# Test_Board.net
KiCad netlist of a schematic drawn in Altium Designer
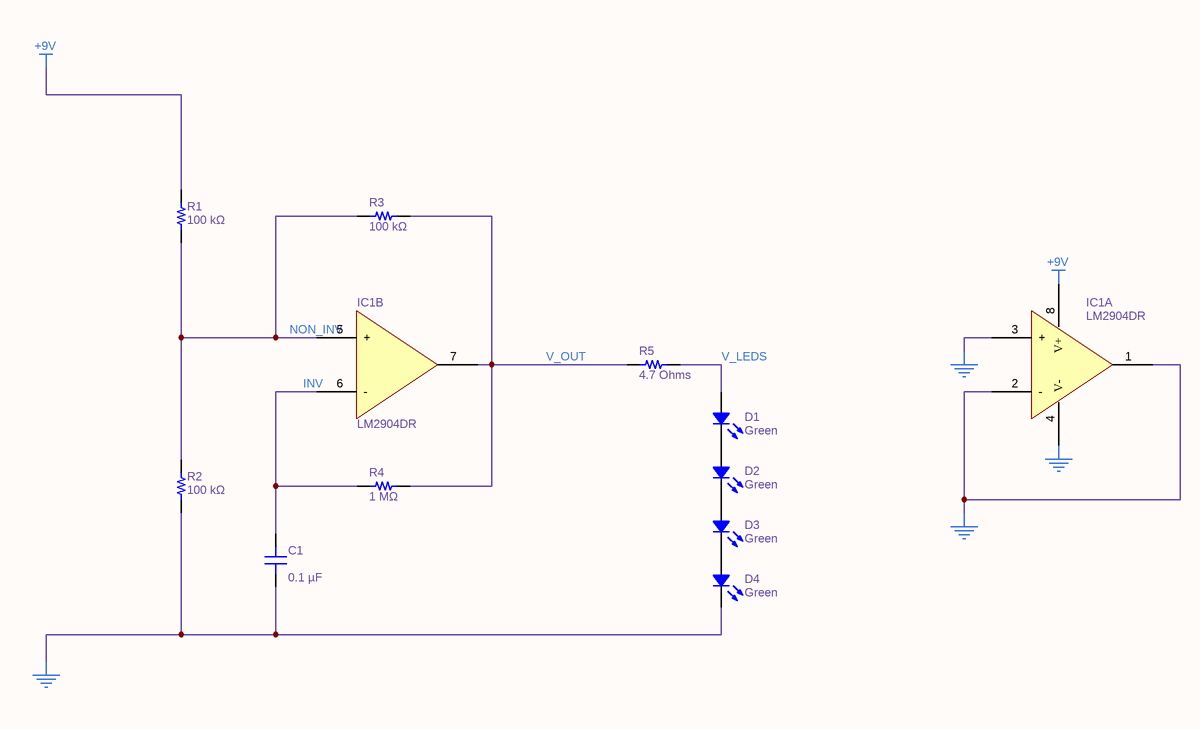
[diagram p0: Test_Board.SchDoc]

(export (version "E")
  (design (tool "Eeschema 10.0.6"))
  (components
    (comp (ref "C1")
      (value "0.1 µF")
      (footprint "MURATA GRM21B 0805_2012")
      (description "CAP CER 0.1UF 10V U2J 0805")
      (fields
        (field (name "PART NUMBER") "GRM21B7U1A104JA01L")
        (field (name "CAPACITANCE") "0.1 µF")
        (field (name "MANUFACTURER") "Murata Electronics")
      )
      (libsource (lib "Celestial Altium Library - altium_library") (part "Capacitor"))
    )
    (comp (ref "D1")
      (value "Green")
      (footprint "LED 0805_2012 GREEN")
      (description "LED GREEN CLEAR SMD")
      (fields (field (name "PART NUMBER") "LTST-C170KGKT") (field (name "MANUFACTURER") "Lite-On Inc."))
      (libsource (lib "Celestial Altium Library - altium_library") (part "LED"))
    )
    (comp (ref "D2")
      (value "Green")
      (footprint "LED 0805_2012 GREEN")
      (description "LED GREEN CLEAR SMD")
      (fields (field (name "PART NUMBER") "LTST-C170KGKT") (field (name "MANUFACTURER") "Lite-On Inc."))
      (libsource (lib "Celestial Altium Library - altium_library") (part "LED"))
    )
    (comp (ref "D3")
      (value "Green")
      (footprint "LED 0805_2012 GREEN")
      (description "LED GREEN CLEAR SMD")
      (fields (field (name "PART NUMBER") "LTST-C170KGKT") (field (name "MANUFACTURER") "Lite-On Inc."))
      (libsource (lib "Celestial Altium Library - altium_library") (part "LED"))
    )
    (comp (ref "D4")
      (value "Green")
      (footprint "LED 0805_2012 GREEN")
      (description "LED GREEN CLEAR SMD")
      (fields (field (name "PART NUMBER") "LTST-C170KGKT") (field (name "MANUFACTURER") "Lite-On Inc."))
      (libsource (lib "Celestial Altium Library - altium_library") (part "LED"))
    )
    (comp (ref "IC1")
      (value "LM2904DR")
      (footprint "TI SOIC-8 D")
      (description "IC OPAMP GP 2 CIRCUIT 8SOIC")
      (fields (field (name "MANUFACTURER") "Texas Instruments"))
      (libsource (lib "Celestial Altium Library - altium_library") (part "TI LM2904DR"))
    )
    (comp (ref "R1")
      (value "100 kΩ")
      (footprint "YAGEO RES 0805_2012")
      (description "RES SMD 100K OHM 0.5% 1/8W 0805")
      (fields (field (name "PART NUMBER") "RT0805DRD07100KL") (field (name "MANUFACTURER") "Yageo"))
      (libsource (lib "Celestial Altium Library - altium_library") (part "Resistor"))
    )
    (comp (ref "R2")
      (value "100 kΩ")
      (footprint "YAGEO RES 0805_2012")
      (description "RES SMD 100K OHM 0.5% 1/8W 0805")
      (fields (field (name "PART NUMBER") "RT0805DRD07100KL") (field (name "MANUFACTURER") "Yageo"))
      (libsource (lib "Celestial Altium Library - altium_library") (part "Resistor"))
    )
    (comp (ref "R3")
      (value "100 kΩ")
      (footprint "YAGEO RES 0805_2012")
      (description "RES SMD 100K OHM 0.5% 1/8W 0805")
      (fields (field (name "PART NUMBER") "RT0805DRD07100KL") (field (name "MANUFACTURER") "Yageo"))
      (libsource (lib "Celestial Altium Library - altium_library") (part "Resistor"))
    )
    (comp (ref "R4")
      (value "1 MΩ")
      (footprint "YAGEO RES 0805_2012")
      (description "RES SMD 1M OHM 0.1% 1/8W 0805")
      (fields (field (name "PART NUMBER") "RT0805BRD071ML") (field (name "MANUFACTURER") "Yageo"))
      (libsource (lib "Celestial Altium Library - altium_library") (part "Resistor"))
    )
    (comp (ref "R5")
      (value "4.7 Ohms")
      (footprint "YAGEO RES 0805_2012")
      (description "RES CHIP 0805")
      (fields (field (name "PART NUMBER") "AC0805FR-7W4R7L") (field (name "MANUFACTURER") "Yageo"))
      (libsource (lib "Celestial Altium Library - altium_library") (part "Resistor"))
    )
  )
  (nets
    (net (code "1") (name "+9V") (class "Default")
      (node (ref "IC1") (pin "8") (pinfunction "V+_8") (pintype "passive"))
      (node (ref "R1") (pin "1") (pinfunction "1_1") (pintype "passive"))
    )
    (net (code "2") (name "/INV") (class "Default")
      (node (ref "C1") (pin "2") (pinfunction "2_2") (pintype "passive"))
      (node (ref "IC1") (pin "6") (pinfunction "-_6") (pintype "passive"))
      (node (ref "R4") (pin "1") (pinfunction "1_1") (pintype "passive"))
    )
    (net (code "3") (name "/NON_INV") (class "Default")
      (node (ref "IC1") (pin "5") (pinfunction "+_5") (pintype "passive"))
      (node (ref "R1") (pin "2") (pinfunction "2_2") (pintype "passive"))
      (node (ref "R2") (pin "1") (pinfunction "1_1") (pintype "passive"))
      (node (ref "R3") (pin "1") (pinfunction "1_1") (pintype "passive"))
    )
    (net (code "4") (name "/V_LEDS") (class "Default")
      (node (ref "D1") (pin "1") (pinfunction "1_1") (pintype "passive"))
      (node (ref "R5") (pin "2") (pinfunction "2_2") (pintype "passive"))
    )
    (net (code "5") (name "/V_OUT") (class "Default")
      (node (ref "IC1") (pin "7") (pinfunction "OUTB_7") (pintype "passive"))
      (node (ref "R3") (pin "2") (pinfunction "2_2") (pintype "passive"))
      (node (ref "R4") (pin "2") (pinfunction "2_2") (pintype "passive"))
      (node (ref "R5") (pin "1") (pinfunction "1_1") (pintype "passive"))
    )
    (net (code "6") (name "GND") (class "Default")
      (node (ref "C1") (pin "1") (pinfunction "1_1") (pintype "passive"))
      (node (ref "D4") (pin "2") (pinfunction "2_2") (pintype "passive"))
      (node (ref "IC1") (pin "1") (pinfunction "OUTA_1") (pintype "passive"))
      (node (ref "IC1") (pin "2") (pinfunction "-_2") (pintype "passive"))
      (node (ref "IC1") (pin "3") (pinfunction "+_3") (pintype "passive"))
      (node (ref "IC1") (pin "4") (pinfunction "V-_4") (pintype "passive"))
      (node (ref "R2") (pin "2") (pinfunction "2_2") (pintype "passive"))
    )
    (net (code "7") (name "Net-(D1-Pad2)") (class "Default")
      (node (ref "D1") (pin "2") (pinfunction "2_2") (pintype "passive"))
      (node (ref "D2") (pin "1") (pinfunction "1_1") (pintype "passive"))
    )
    (net (code "8") (name "Net-(D2-Pad2)") (class "Default")
      (node (ref "D2") (pin "2") (pinfunction "2_2") (pintype "passive"))
      (node (ref "D3") (pin "1") (pinfunction "1_1") (pintype "passive"))
    )
    (net (code "9") (name "Net-(D3-Pad2)") (class "Default")
      (node (ref "D3") (pin "2") (pinfunction "2_2") (pintype "passive"))
      (node (ref "D4") (pin "1") (pinfunction "1_1") (pintype "passive"))
    )
  )
)
